# light_humid.net
KiCad netlist of a schematic drawn in Altium Designer
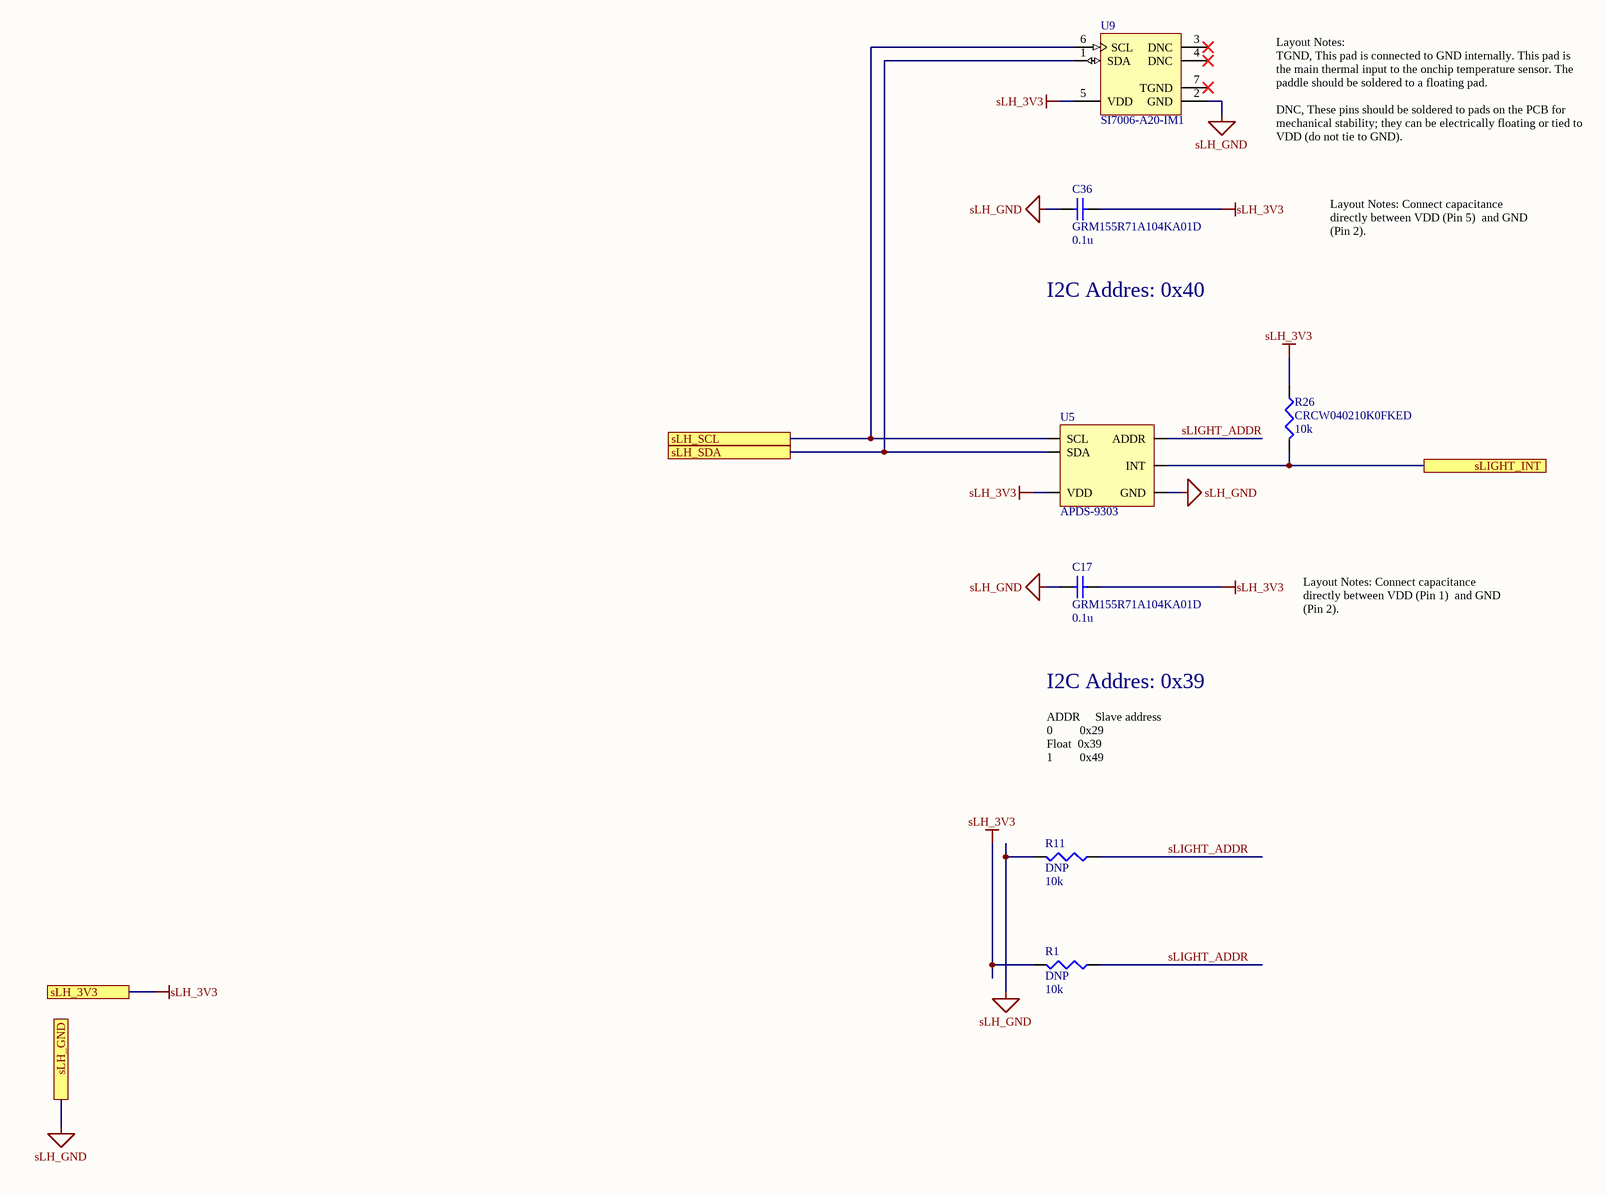
[diagram p0: _light_humid.SchDoc]

(export (version "E")
  (design (tool "Eeschema 10.0.6"))
  (components
    (comp (ref "C17")
      (value "GRM155R71A104KA01D")
      (footprint "0402")
      (description "-55-125C, 1005, 10V, X7R, ±10%")
      (fields (field (name "ALTIUM_VALUE") "0.1u"))
      (libsource (lib "standard_capacitors") (part "GRM155R71AxxxKdddd"))
    )
    (comp (ref "C36")
      (value "GRM155R71A104KA01D")
      (footprint "0402")
      (description "-55-125C, 1005, 10V, X7R, ±10%")
      (fields (field (name "ALTIUM_VALUE") "0.1u"))
      (libsource (lib "standard_capacitors") (part "GRM155R71AxxxKdddd"))
    )
    (comp (ref "R1")
      (value "DNP")
      (footprint "0402")
      (description "0.125W, -55-155C, 1005, 50V, ±1%")
      (fields (field (name "ALTIUM_VALUE") "10k"))
      (libsource (lib "standard_resistors") (part "CRCW0402xxxxFKED"))
    )
    (comp (ref "R11")
      (value "DNP")
      (footprint "0402")
      (description "0.125W, -55-155C, 1005, 50V, ±1%")
      (fields (field (name "ALTIUM_VALUE") "10k"))
      (libsource (lib "standard_resistors") (part "CRCW0402xxxxFKED"))
    )
    (comp (ref "R26")
      (value "CRCW040210K0FKED")
      (footprint "0402")
      (description "0.125W, -55-155C, 1005, 50V, ±1%")
      (fields (field (name "ALTIUM_VALUE") "10k"))
      (libsource (lib "standard_resistors") (part "CRCW0402xxxxFKED"))
    )
    (comp (ref "U5") (value "APDS-9303") (footprint "APDS-9303") (libsource (lib "avago") (part "APDS-9303")))
    (comp (ref "U9")
      (value "SI7006-A20-IM1")
      (footprint "SLAB-DFN-6-1500X2400TP_V")
      (description "I2C Humidity and Temperature Sensor, 1.9 to 3.6 V, -40 to 125 degC, 6-Pin DFN, RoHS, Tube")
      (fields (field (name "MANUFACTURER") "Silicon Labs"))
      (libsource (lib "Altium Content Vault") (part "CMP-2000-07060-1"))
    )
  )
  (nets
    (net (code "1") (name "/sLH_SCL") (class "Default")
      (node (ref "U5") (pin "4") (pinfunction "SCL_4") (pintype "passive"))
      (node (ref "U9") (pin "6") (pinfunction "SCL_6") (pintype "input"))
    )
    (net (code "2") (name "/sLH_SDA") (class "Default")
      (node (ref "U5") (pin "5") (pinfunction "SDA_5") (pintype "passive"))
      (node (ref "U9") (pin "1") (pinfunction "SDA_1") (pintype "bidirectional"))
    )
    (net (code "3") (name "/sLIGHT_ADDR") (class "Default")
      (node (ref "R1") (pin "1") (pinfunction "1_1") (pintype "passive"))
      (node (ref "R11") (pin "1") (pinfunction "1_1") (pintype "passive"))
      (node (ref "U5") (pin "3") (pinfunction "ADDR_3") (pintype "passive"))
    )
    (net (code "4") (name "/sLIGHT_INT") (class "Default")
      (node (ref "R26") (pin "2") (pinfunction "2_2") (pintype "passive"))
      (node (ref "U5") (pin "6") (pinfunction "INT_6") (pintype "passive"))
    )
    (net (code "5") (name "sLH_3V3") (class "Default")
      (node (ref "C17") (pin "2") (pinfunction "2_2") (pintype "passive"))
      (node (ref "C36") (pin "2") (pinfunction "2_2") (pintype "passive"))
      (node (ref "R1") (pin "2") (pinfunction "2_2") (pintype "passive"))
      (node (ref "R26") (pin "1") (pinfunction "1_1") (pintype "passive"))
      (node (ref "U5") (pin "1") (pinfunction "VDD_1") (pintype "passive"))
      (node (ref "U9") (pin "5") (pinfunction "VDD_5") (pintype "power_in"))
    )
    (net (code "6") (name "sLH_GND") (class "Default")
      (node (ref "C17") (pin "1") (pinfunction "1_1") (pintype "passive"))
      (node (ref "C36") (pin "1") (pinfunction "1_1") (pintype "passive"))
      (node (ref "R11") (pin "2") (pinfunction "2_2") (pintype "passive"))
      (node (ref "U5") (pin "2") (pinfunction "GND_2") (pintype "passive"))
      (node (ref "U9") (pin "2") (pinfunction "GND_2") (pintype "power_in"))
    )
    (net (code "7") (name "unconnected-(U9-DNC-Pad3)") (class "Default")
      (node (ref "U9") (pin "3") (pinfunction "DNC_3") (pintype "passive+no_connect"))
    )
    (net (code "8") (name "unconnected-(U9-DNC-Pad4)") (class "Default")
      (node (ref "U9") (pin "4") (pinfunction "DNC_4") (pintype "passive+no_connect"))
    )
    (net (code "9") (name "unconnected-(U9-TGND-Pad7)") (class "Default")
      (node (ref "U9") (pin "7") (pinfunction "TGND_7") (pintype "power_in+no_connect"))
    )
  )
)
